# WLED_MINI_v0_92.net
KiCad netlist of a schematic drawn in EAGLE
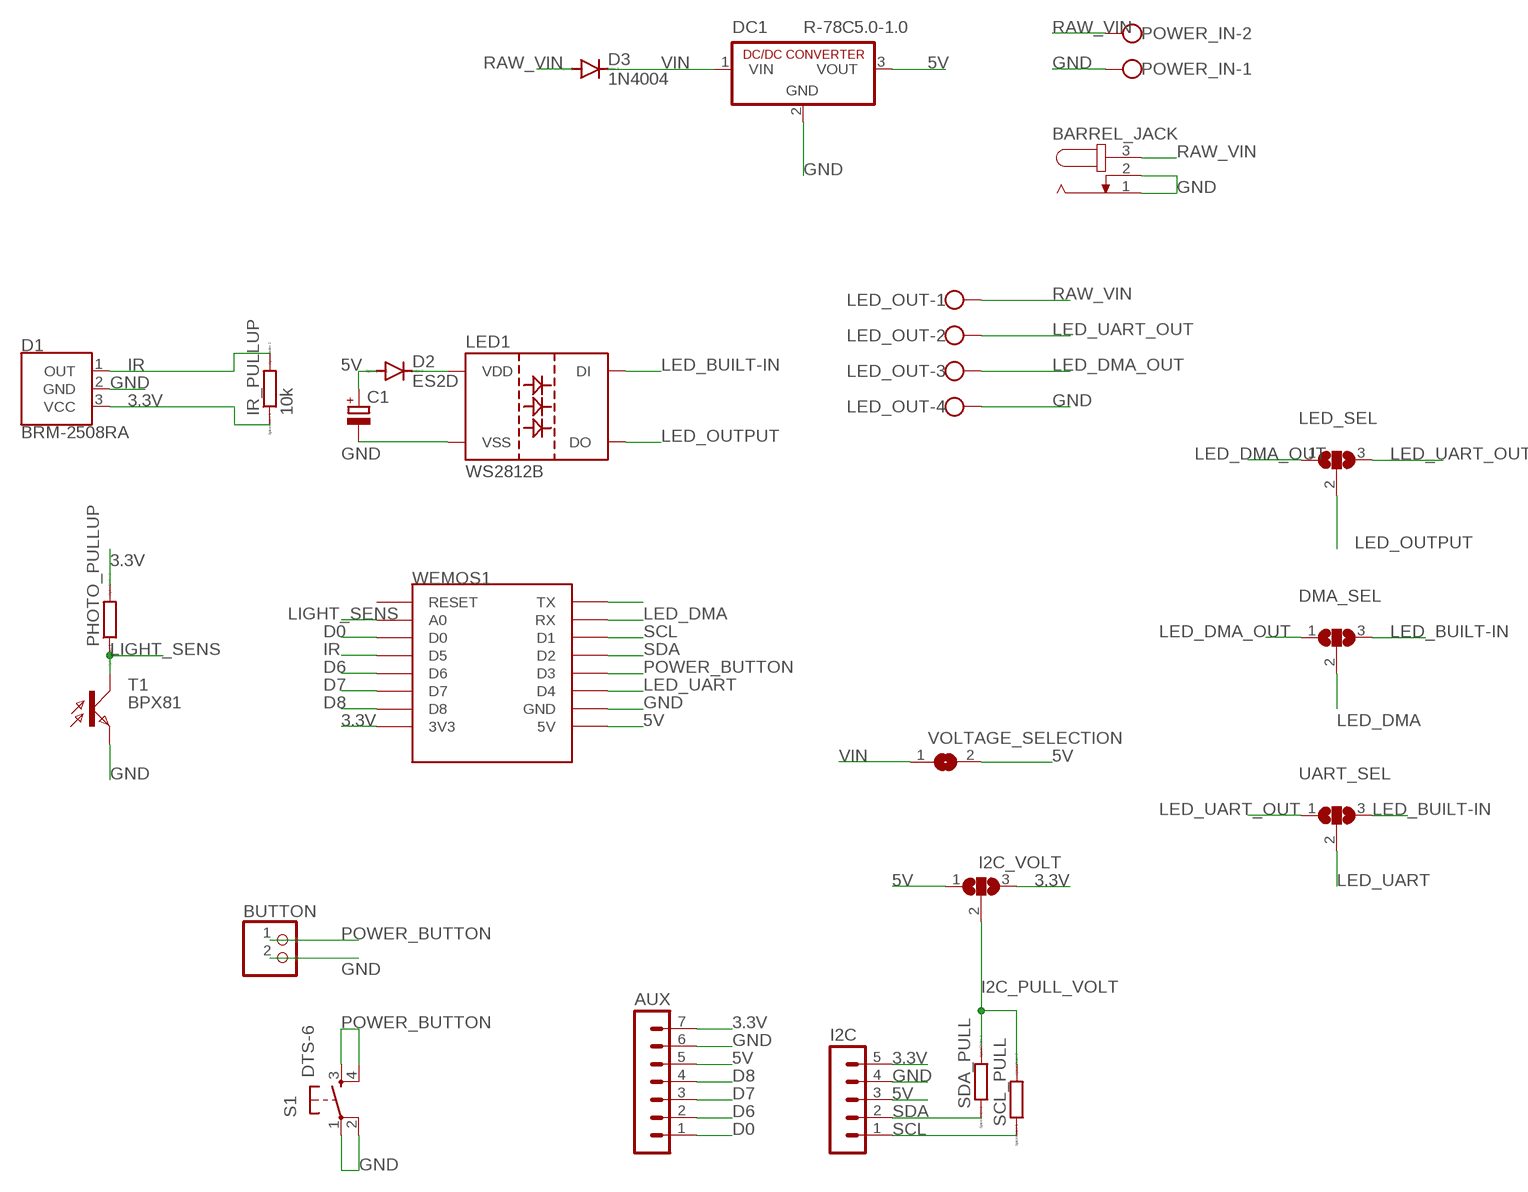
[diagram p0: schematic, sheet 1]

(export (version "E")
  (design (tool "Eeschema 10.0.6"))
  (components
    (comp (ref "AUX")
      (value "MA07-1")
      (footprint "eagle-import:MA07-1")
      (libsource (lib "eagle-import") (part "MA07-1"))
    )
    (comp (ref "BARREL_JACK")
      (value "JACK-PLUG0")
      (footprint "eagle-import:SPC4077")
      (libsource (lib "eagle-import") (part "JACK-PLUG0"))
    )
    (comp (ref "BUTTON")
      (value "PINHD-1X2")
      (footprint "eagle-import:1X02")
      (libsource (lib "eagle-import") (part "PINHD-1X2"))
    )
    (comp (ref "C1")
      (value "CPOL-EUE2.5-7")
      (footprint "eagle-import:E2,5-7")
      (libsource (lib "eagle-import") (part "CPOL-EUE2.5-7"))
    )
    (comp (ref "D1")
      (value "BRM-2508RA")
      (footprint "eagle-import:BRM-2508")
      (libsource (lib "eagle-import") (part "BRM-2508RA"))
    )
    (comp (ref "D2")
      (value "ES2D")
      (footprint "eagle-import:SMB")
      (libsource (lib "eagle-import") (part "ES2D"))
    )
    (comp (ref "D3")
      (value "1N4004")
      (footprint "eagle-import:DO41-10")
      (libsource (lib "eagle-import") (part "1N4004"))
    )
    (comp (ref "DC1")
      (value "R-78C5.0-1.0")
      (footprint "eagle-import:SIP3")
      (libsource (lib "eagle-import") (part "R-78C-1.05.0"))
    )
    (comp (ref "DMA_SEL")
      (value "SJ2W")
      (footprint "eagle-import:SJ_2")
      (libsource (lib "eagle-import") (part "SJ2W"))
    )
    (comp (ref "I2C")
      (value "MA05-1")
      (footprint "eagle-import:MA05-1")
      (libsource (lib "eagle-import") (part "MA05-1"))
    )
    (comp (ref "I2C_VOLT")
      (value "SJ2W")
      (footprint "eagle-import:SJ_2")
      (libsource (lib "eagle-import") (part "SJ2W"))
    )
    (comp (ref "IR_PULLUP")
      (value "10k")
      (footprint "eagle-import:0204_7")
      (libsource (lib "eagle-import") (part "R0204/7"))
    )
    (comp (ref "LED1")
      (value "WS2812B")
      (footprint "eagle-import:WS2812B")
      (libsource (lib "eagle-import") (part "WS2812B"))
    )
    (comp (ref "LED_OUT")
      (value "W237-4")
      (footprint "eagle-import:W237-4")
      (libsource (lib "eagle-import") (part "W237-4"))
    )
    (comp (ref "LED_SEL")
      (value "SJ2W")
      (footprint "eagle-import:SJ_2")
      (libsource (lib "eagle-import") (part "SJ2W"))
    )
    (comp (ref "PHOTO_PULLUP")
      (value "R0204/7")
      (footprint "eagle-import:0204_7")
      (libsource (lib "eagle-import") (part "R0204/7"))
    )
    (comp (ref "POWER_IN")
      (value "W237-102")
      (footprint "eagle-import:W237-102")
      (fields (field (name "MPN") "237-102"))
      (libsource (lib "eagle-import") (part "W237-102"))
    )
    (comp (ref "S1")
      (value "DTS-6")
      (footprint "eagle-import:DTS-6")
      (libsource (lib "eagle-import") (part "DTS-6"))
    )
    (comp (ref "SCL_PULL")
      (value "R0204/7")
      (footprint "eagle-import:0204_7")
      (libsource (lib "eagle-import") (part "R0204/7"))
    )
    (comp (ref "SDA_PULL")
      (value "R0204/7")
      (footprint "eagle-import:0204_7")
      (libsource (lib "eagle-import") (part "R0204/7"))
    )
    (comp (ref "T1")
      (value "BPX81")
      (footprint "eagle-import:BPX81")
      (libsource (lib "eagle-import") (part "BPX81"))
    )
    (comp (ref "UART_SEL")
      (value "SJ2W")
      (footprint "eagle-import:SJ_2")
      (libsource (lib "eagle-import") (part "SJ2W"))
    )
    (comp (ref "VOLTAGE_SELECTION")
      (value "SJ")
      (footprint "eagle-import:SJ")
      (libsource (lib "eagle-import") (part "SJ"))
    )
    (comp (ref "WEMOS1")
      (value "WEMOS-D1-MINI")
      (footprint "eagle-import:WEMOS-D1-MINI")
      (libsource (lib "eagle-import") (part "WEMOS-D1-MINI"))
    )
  )
  (nets
    (net (code "1") (name "/3.3V") (class "Default")
      (node (ref "AUX") (pin "7") (pinfunction "7_7") (pintype "passive"))
      (node (ref "D1") (pin "3") (pinfunction "VCC_3") (pintype "bidirectional"))
      (node (ref "I2C") (pin "5") (pinfunction "5_5") (pintype "passive"))
      (node (ref "I2C_VOLT") (pin "3") (pinfunction "3_3") (pintype "passive"))
      (node (ref "IR_PULLUP") (pin "1") (pinfunction "1_1") (pintype "passive"))
      (node (ref "PHOTO_PULLUP") (pin "2") (pinfunction "2_2") (pintype "passive"))
      (node (ref "WEMOS1") (pin "3V3") (pinfunction "3V3_3V3") (pintype "bidirectional"))
    )
    (net (code "2") (name "/5V") (class "Default")
      (node (ref "AUX") (pin "5") (pinfunction "5_5") (pintype "passive"))
      (node (ref "C1") (pin "+") (pinfunction "+_+") (pintype "passive"))
      (node (ref "D2") (pin "A") (pinfunction "A_A") (pintype "passive"))
      (node (ref "DC1") (pin "3") (pinfunction "VOUT_3") (pintype "passive"))
      (node (ref "I2C") (pin "3") (pinfunction "3_3") (pintype "passive"))
      (node (ref "I2C_VOLT") (pin "1") (pinfunction "1_1") (pintype "passive"))
      (node (ref "VOLTAGE_SELECTION") (pin "2") (pinfunction "2_2") (pintype "passive"))
      (node (ref "WEMOS1") (pin "5V") (pinfunction "5V_5V") (pintype "bidirectional"))
    )
    (net (code "3") (name "/D0") (class "Default")
      (node (ref "AUX") (pin "1") (pinfunction "1_1") (pintype "passive"))
      (node (ref "WEMOS1") (pin "D0") (pinfunction "D0_D0") (pintype "bidirectional"))
    )
    (net (code "4") (name "/D6") (class "Default")
      (node (ref "AUX") (pin "2") (pinfunction "2_2") (pintype "passive"))
      (node (ref "WEMOS1") (pin "D6") (pinfunction "D6_D6") (pintype "bidirectional"))
    )
    (net (code "5") (name "/D7") (class "Default")
      (node (ref "AUX") (pin "3") (pinfunction "3_3") (pintype "passive"))
      (node (ref "WEMOS1") (pin "D7") (pinfunction "D7_D7") (pintype "bidirectional"))
    )
    (net (code "6") (name "/D8") (class "Default")
      (node (ref "AUX") (pin "4") (pinfunction "4_4") (pintype "passive"))
      (node (ref "WEMOS1") (pin "D8") (pinfunction "D8_D8") (pintype "bidirectional"))
    )
    (net (code "7") (name "/GND") (class "Default")
      (node (ref "AUX") (pin "6") (pinfunction "6_6") (pintype "passive"))
      (node (ref "BARREL_JACK") (pin "1") (pinfunction "1_1") (pintype "passive"))
      (node (ref "BARREL_JACK") (pin "2") (pinfunction "2_2") (pintype "passive"))
      (node (ref "BUTTON") (pin "2") (pinfunction "2_2") (pintype "passive"))
      (node (ref "C1") (pin "-") (pinfunction "-_-") (pintype "passive"))
      (node (ref "D1") (pin "2") (pinfunction "GND_2") (pintype "bidirectional"))
      (node (ref "DC1") (pin "2") (pinfunction "GND_2") (pintype "passive"))
      (node (ref "I2C") (pin "4") (pinfunction "4_4") (pintype "passive"))
      (node (ref "LED1") (pin "3") (pinfunction "VSS_3") (pintype "bidirectional"))
      (node (ref "LED_OUT") (pin "4") (pinfunction "KL_4") (pintype "passive"))
      (node (ref "POWER_IN") (pin "1") (pinfunction "KL_1") (pintype "passive"))
      (node (ref "S1") (pin "1") (pinfunction "1_1") (pintype "passive"))
      (node (ref "S1") (pin "2") (pinfunction "2_2") (pintype "passive"))
      (node (ref "T1") (pin "E") (pinfunction "E_E") (pintype "passive"))
      (node (ref "WEMOS1") (pin "GND") (pinfunction "GND_GND") (pintype "bidirectional"))
    )
    (net (code "8") (name "/I2C_PULL_VOLT") (class "Default")
      (node (ref "I2C_VOLT") (pin "2") (pinfunction "2_2") (pintype "passive"))
      (node (ref "SCL_PULL") (pin "2") (pinfunction "2_2") (pintype "passive"))
      (node (ref "SDA_PULL") (pin "2") (pinfunction "2_2") (pintype "passive"))
    )
    (net (code "9") (name "/IR") (class "Default")
      (node (ref "D1") (pin "1") (pinfunction "OUT_1") (pintype "bidirectional"))
      (node (ref "IR_PULLUP") (pin "2") (pinfunction "2_2") (pintype "passive"))
      (node (ref "WEMOS1") (pin "D5") (pinfunction "D5_D5") (pintype "bidirectional"))
    )
    (net (code "10") (name "/LED_BUILT-IN") (class "Default")
      (node (ref "DMA_SEL") (pin "3") (pinfunction "3_3") (pintype "passive"))
      (node (ref "LED1") (pin "4") (pinfunction "DI_4") (pintype "bidirectional"))
      (node (ref "UART_SEL") (pin "3") (pinfunction "3_3") (pintype "passive"))
    )
    (net (code "11") (name "/LED_DMA") (class "Default")
      (node (ref "DMA_SEL") (pin "2") (pinfunction "2_2") (pintype "passive"))
      (node (ref "WEMOS1") (pin "RX") (pinfunction "RX_RX") (pintype "bidirectional"))
    )
    (net (code "12") (name "/LED_DMA_OUT") (class "Default")
      (node (ref "DMA_SEL") (pin "1") (pinfunction "1_1") (pintype "passive"))
      (node (ref "LED_OUT") (pin "3") (pinfunction "KL_3") (pintype "passive"))
      (node (ref "LED_SEL") (pin "1") (pinfunction "1_1") (pintype "passive"))
    )
    (net (code "13") (name "/LED_OUTPUT") (class "Default")
      (node (ref "LED1") (pin "2") (pinfunction "DO_2") (pintype "bidirectional"))
      (node (ref "LED_SEL") (pin "2") (pinfunction "2_2") (pintype "passive"))
    )
    (net (code "14") (name "/LED_UART") (class "Default")
      (node (ref "UART_SEL") (pin "2") (pinfunction "2_2") (pintype "passive"))
      (node (ref "WEMOS1") (pin "D4") (pinfunction "D4_D4") (pintype "bidirectional"))
    )
    (net (code "15") (name "/LED_UART_OUT") (class "Default")
      (node (ref "LED_OUT") (pin "2") (pinfunction "KL_2") (pintype "passive"))
      (node (ref "LED_SEL") (pin "3") (pinfunction "3_3") (pintype "passive"))
      (node (ref "UART_SEL") (pin "1") (pinfunction "1_1") (pintype "passive"))
    )
    (net (code "16") (name "/LIGHT_SENS") (class "Default")
      (node (ref "PHOTO_PULLUP") (pin "1") (pinfunction "1_1") (pintype "passive"))
      (node (ref "T1") (pin "C") (pinfunction "C_C") (pintype "passive"))
      (node (ref "WEMOS1") (pin "A0") (pinfunction "A0_A0") (pintype "bidirectional"))
    )
    (net (code "17") (name "/POWER_BUTTON") (class "Default")
      (node (ref "BUTTON") (pin "1") (pinfunction "1_1") (pintype "passive"))
      (node (ref "S1") (pin "3") (pinfunction "3_3") (pintype "passive"))
      (node (ref "S1") (pin "4") (pinfunction "4_4") (pintype "passive"))
      (node (ref "WEMOS1") (pin "D3") (pinfunction "D3_D3") (pintype "bidirectional"))
    )
    (net (code "18") (name "/RAW_VIN") (class "Default")
      (node (ref "BARREL_JACK") (pin "3") (pinfunction "3_3") (pintype "passive"))
      (node (ref "D3") (pin "A") (pinfunction "A_A") (pintype "passive"))
      (node (ref "LED_OUT") (pin "1") (pinfunction "KL_1") (pintype "passive"))
      (node (ref "POWER_IN") (pin "2") (pinfunction "KL_2") (pintype "passive"))
    )
    (net (code "19") (name "/SCL") (class "Default")
      (node (ref "I2C") (pin "1") (pinfunction "1_1") (pintype "passive"))
      (node (ref "SCL_PULL") (pin "1") (pinfunction "1_1") (pintype "passive"))
      (node (ref "WEMOS1") (pin "D1") (pinfunction "D1_D1") (pintype "bidirectional"))
    )
    (net (code "20") (name "/SDA") (class "Default")
      (node (ref "I2C") (pin "2") (pinfunction "2_2") (pintype "passive"))
      (node (ref "SDA_PULL") (pin "1") (pinfunction "1_1") (pintype "passive"))
      (node (ref "WEMOS1") (pin "D2") (pinfunction "D2_D2") (pintype "bidirectional"))
    )
    (net (code "21") (name "/VIN") (class "Default")
      (node (ref "D3") (pin "C") (pinfunction "C_C") (pintype "passive"))
      (node (ref "DC1") (pin "1") (pinfunction "VIN_1") (pintype "passive"))
      (node (ref "VOLTAGE_SELECTION") (pin "1") (pinfunction "1_1") (pintype "passive"))
    )
    (net (code "22") (name "Net-(LED1-VDD)") (class "Default")
      (node (ref "D2") (pin "C") (pinfunction "C_C") (pintype "passive"))
      (node (ref "LED1") (pin "1") (pinfunction "VDD_1") (pintype "bidirectional"))
    )
    (net (code "23") (name "unconnected-(WEMOS1-PadRESET)") (class "Default")
      (node (ref "WEMOS1") (pin "RESET") (pinfunction "RESET_RESET") (pintype "bidirectional"))
    )
    (net (code "24") (name "unconnected-(WEMOS1-PadTX)") (class "Default")
      (node (ref "WEMOS1") (pin "TX") (pinfunction "TX_TX") (pintype "bidirectional"))
    )
  )
)
